# fretscanner-untangle2.net
KiCad netlist of a schematic drawn in EAGLE
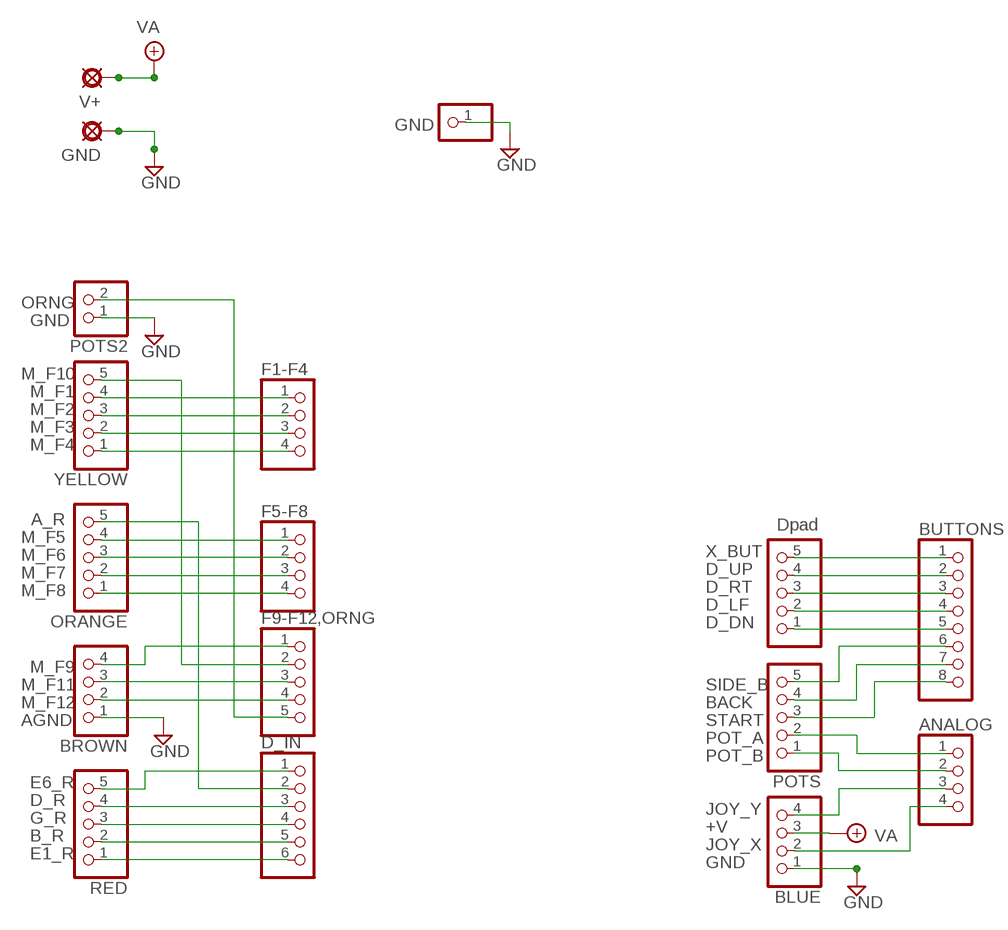
[diagram p0: schematic, sheet 1]

(export (version "E")
  (design (tool "Eeschema 10.0.6"))
  (components
    (comp (ref "ANALOG")
      (value "PINHD-1X4")
      (footprint "eagle-import:1X04")
      (libsource (lib "eagle-import") (part "PINHD-1X4"))
    )
    (comp (ref "BLUE")
      (value "PINHD-1X4")
      (footprint "eagle-import:1X04")
      (libsource (lib "eagle-import") (part "PINHD-1X4"))
    )
    (comp (ref "BROWN")
      (value "PINHD-1X4")
      (footprint "eagle-import:1X04")
      (libsource (lib "eagle-import") (part "PINHD-1X4"))
    )
    (comp (ref "BUTTONS")
      (value "PINHD-1X8")
      (footprint "eagle-import:1X08")
      (libsource (lib "eagle-import") (part "PINHD-1X8"))
    )
    (comp (ref "DPAD")
      (value "PINHD-1X5")
      (footprint "eagle-import:1X05")
      (libsource (lib "eagle-import") (part "PINHD-1X5"))
    )
    (comp (ref "DPAD2")
      (value "PINHD-1X1")
      (footprint "eagle-import:1X01")
      (libsource (lib "eagle-import") (part "PINHD-1X1"))
    )
    (comp (ref "D_IN")
      (value "PINHD-1X6")
      (footprint "eagle-import:1X06")
      (libsource (lib "eagle-import") (part "PINHD-1X6"))
    )
    (comp (ref "F1-F4")
      (value "PINHD-1X4")
      (footprint "eagle-import:1X04")
      (libsource (lib "eagle-import") (part "PINHD-1X4"))
    )
    (comp (ref "F5-F8")
      (value "PINHD-1X4")
      (footprint "eagle-import:1X04")
      (libsource (lib "eagle-import") (part "PINHD-1X4"))
    )
    (comp (ref "F9-F12,ORNG")
      (value "PINHD-1X5")
      (footprint "eagle-import:1X05")
      (libsource (lib "eagle-import") (part "PINHD-1X5"))
    )
    (comp (ref "GND")
      (value "PADL")
      (footprint "eagle-import:LONG")
      (libsource (lib "eagle-import") (part "PADL"))
    )
    (comp (ref "ORANGE")
      (value "PINHD-1X5")
      (footprint "eagle-import:1X05")
      (libsource (lib "eagle-import") (part "PINHD-1X5"))
    )
    (comp (ref "POTS")
      (value "PINHD-1X5")
      (footprint "eagle-import:1X05")
      (libsource (lib "eagle-import") (part "PINHD-1X5"))
    )
    (comp (ref "POTS2")
      (value "PINHD-1X2")
      (footprint "eagle-import:1X02")
      (libsource (lib "eagle-import") (part "PINHD-1X2"))
    )
    (comp (ref "RED")
      (value "PINHD-1X5")
      (footprint "eagle-import:1X05")
      (libsource (lib "eagle-import") (part "PINHD-1X5"))
    )
    (comp (ref "V+")
      (value "PADL")
      (footprint "eagle-import:LONG")
      (libsource (lib "eagle-import") (part "PADL"))
    )
    (comp (ref "YELLOW")
      (value "PINHD-1X5")
      (footprint "eagle-import:1X05")
      (libsource (lib "eagle-import") (part "PINHD-1X5"))
    )
  )
  (nets
    (net (code "1") (name "GND") (class "Default")
      (node (ref "BLUE") (pin "1") (pinfunction "1_1") (pintype "passive"))
      (node (ref "BROWN") (pin "1") (pinfunction "1_1") (pintype "passive"))
      (node (ref "DPAD2") (pin "1") (pinfunction "1_1") (pintype "passive"))
      (node (ref "GND") (pin "1") (pinfunction "PAD_1") (pintype "passive"))
      (node (ref "POTS2") (pin "1") (pinfunction "1_1") (pintype "passive"))
    )
    (net (code "2") (name "Net-(ANALOG-Pad1)") (class "Default")
      (node (ref "ANALOG") (pin "1") (pinfunction "1_1") (pintype "passive"))
      (node (ref "POTS") (pin "2") (pinfunction "2_2") (pintype "passive"))
    )
    (net (code "3") (name "Net-(ANALOG-Pad2)") (class "Default")
      (node (ref "ANALOG") (pin "2") (pinfunction "2_2") (pintype "passive"))
      (node (ref "POTS") (pin "1") (pinfunction "1_1") (pintype "passive"))
    )
    (net (code "4") (name "Net-(ANALOG-Pad3)") (class "Default")
      (node (ref "ANALOG") (pin "3") (pinfunction "3_3") (pintype "passive"))
      (node (ref "BLUE") (pin "4") (pinfunction "4_4") (pintype "passive"))
    )
    (net (code "5") (name "Net-(ANALOG-Pad4)") (class "Default")
      (node (ref "ANALOG") (pin "4") (pinfunction "4_4") (pintype "passive"))
      (node (ref "BLUE") (pin "2") (pinfunction "2_2") (pintype "passive"))
    )
    (net (code "6") (name "Net-(BROWN-Pad2)") (class "Default")
      (node (ref "BROWN") (pin "2") (pinfunction "2_2") (pintype "passive"))
      (node (ref "F9-F12,ORNG") (pin "4") (pinfunction "4_4") (pintype "passive"))
    )
    (net (code "7") (name "Net-(BROWN-Pad3)") (class "Default")
      (node (ref "BROWN") (pin "3") (pinfunction "3_3") (pintype "passive"))
      (node (ref "F9-F12,ORNG") (pin "3") (pinfunction "3_3") (pintype "passive"))
    )
    (net (code "8") (name "Net-(BROWN-Pad4)") (class "Default")
      (node (ref "BROWN") (pin "4") (pinfunction "4_4") (pintype "passive"))
      (node (ref "F9-F12,ORNG") (pin "1") (pinfunction "1_1") (pintype "passive"))
    )
    (net (code "9") (name "Net-(BUTTONS-Pad1)") (class "Default")
      (node (ref "BUTTONS") (pin "1") (pinfunction "1_1") (pintype "passive"))
      (node (ref "DPAD") (pin "5") (pinfunction "5_5") (pintype "passive"))
    )
    (net (code "10") (name "Net-(BUTTONS-Pad2)") (class "Default")
      (node (ref "BUTTONS") (pin "2") (pinfunction "2_2") (pintype "passive"))
      (node (ref "DPAD") (pin "4") (pinfunction "4_4") (pintype "passive"))
    )
    (net (code "11") (name "Net-(BUTTONS-Pad3)") (class "Default")
      (node (ref "BUTTONS") (pin "3") (pinfunction "3_3") (pintype "passive"))
      (node (ref "DPAD") (pin "3") (pinfunction "3_3") (pintype "passive"))
    )
    (net (code "12") (name "Net-(BUTTONS-Pad4)") (class "Default")
      (node (ref "BUTTONS") (pin "4") (pinfunction "4_4") (pintype "passive"))
      (node (ref "DPAD") (pin "2") (pinfunction "2_2") (pintype "passive"))
    )
    (net (code "13") (name "Net-(BUTTONS-Pad5)") (class "Default")
      (node (ref "BUTTONS") (pin "5") (pinfunction "5_5") (pintype "passive"))
      (node (ref "DPAD") (pin "1") (pinfunction "1_1") (pintype "passive"))
    )
    (net (code "14") (name "Net-(BUTTONS-Pad6)") (class "Default")
      (node (ref "BUTTONS") (pin "6") (pinfunction "6_6") (pintype "passive"))
      (node (ref "POTS") (pin "5") (pinfunction "5_5") (pintype "passive"))
    )
    (net (code "15") (name "Net-(BUTTONS-Pad7)") (class "Default")
      (node (ref "BUTTONS") (pin "7") (pinfunction "7_7") (pintype "passive"))
      (node (ref "POTS") (pin "4") (pinfunction "4_4") (pintype "passive"))
    )
    (net (code "16") (name "Net-(BUTTONS-Pad8)") (class "Default")
      (node (ref "BUTTONS") (pin "8") (pinfunction "8_8") (pintype "passive"))
      (node (ref "POTS") (pin "3") (pinfunction "3_3") (pintype "passive"))
    )
    (net (code "17") (name "Net-(D_IN-Pad1)") (class "Default")
      (node (ref "D_IN") (pin "1") (pinfunction "1_1") (pintype "passive"))
      (node (ref "RED") (pin "5") (pinfunction "5_5") (pintype "passive"))
    )
    (net (code "18") (name "Net-(D_IN-Pad2)") (class "Default")
      (node (ref "D_IN") (pin "2") (pinfunction "2_2") (pintype "passive"))
      (node (ref "ORANGE") (pin "5") (pinfunction "5_5") (pintype "passive"))
    )
    (net (code "19") (name "Net-(D_IN-Pad3)") (class "Default")
      (node (ref "D_IN") (pin "3") (pinfunction "3_3") (pintype "passive"))
      (node (ref "RED") (pin "4") (pinfunction "4_4") (pintype "passive"))
    )
    (net (code "20") (name "Net-(D_IN-Pad4)") (class "Default")
      (node (ref "D_IN") (pin "4") (pinfunction "4_4") (pintype "passive"))
      (node (ref "RED") (pin "3") (pinfunction "3_3") (pintype "passive"))
    )
    (net (code "21") (name "Net-(D_IN-Pad5)") (class "Default")
      (node (ref "D_IN") (pin "5") (pinfunction "5_5") (pintype "passive"))
      (node (ref "RED") (pin "2") (pinfunction "2_2") (pintype "passive"))
    )
    (net (code "22") (name "Net-(D_IN-Pad6)") (class "Default")
      (node (ref "D_IN") (pin "6") (pinfunction "6_6") (pintype "passive"))
      (node (ref "RED") (pin "1") (pinfunction "1_1") (pintype "passive"))
    )
    (net (code "23") (name "Net-(F1-F4-Pad1)") (class "Default")
      (node (ref "F1-F4") (pin "1") (pinfunction "1_1") (pintype "passive"))
      (node (ref "YELLOW") (pin "4") (pinfunction "4_4") (pintype "passive"))
    )
    (net (code "24") (name "Net-(F1-F4-Pad2)") (class "Default")
      (node (ref "F1-F4") (pin "2") (pinfunction "2_2") (pintype "passive"))
      (node (ref "YELLOW") (pin "3") (pinfunction "3_3") (pintype "passive"))
    )
    (net (code "25") (name "Net-(F1-F4-Pad3)") (class "Default")
      (node (ref "F1-F4") (pin "3") (pinfunction "3_3") (pintype "passive"))
      (node (ref "YELLOW") (pin "2") (pinfunction "2_2") (pintype "passive"))
    )
    (net (code "26") (name "Net-(F1-F4-Pad4)") (class "Default")
      (node (ref "F1-F4") (pin "4") (pinfunction "4_4") (pintype "passive"))
      (node (ref "YELLOW") (pin "1") (pinfunction "1_1") (pintype "passive"))
    )
    (net (code "27") (name "Net-(F5-F8-Pad1)") (class "Default")
      (node (ref "F5-F8") (pin "1") (pinfunction "1_1") (pintype "passive"))
      (node (ref "ORANGE") (pin "4") (pinfunction "4_4") (pintype "passive"))
    )
    (net (code "28") (name "Net-(F5-F8-Pad2)") (class "Default")
      (node (ref "F5-F8") (pin "2") (pinfunction "2_2") (pintype "passive"))
      (node (ref "ORANGE") (pin "3") (pinfunction "3_3") (pintype "passive"))
    )
    (net (code "29") (name "Net-(F5-F8-Pad3)") (class "Default")
      (node (ref "F5-F8") (pin "3") (pinfunction "3_3") (pintype "passive"))
      (node (ref "ORANGE") (pin "2") (pinfunction "2_2") (pintype "passive"))
    )
    (net (code "30") (name "Net-(F5-F8-Pad4)") (class "Default")
      (node (ref "F5-F8") (pin "4") (pinfunction "4_4") (pintype "passive"))
      (node (ref "ORANGE") (pin "1") (pinfunction "1_1") (pintype "passive"))
    )
    (net (code "31") (name "Net-(F9-F12,ORNG-Pad2)") (class "Default")
      (node (ref "F9-F12,ORNG") (pin "2") (pinfunction "2_2") (pintype "passive"))
      (node (ref "YELLOW") (pin "5") (pinfunction "5_5") (pintype "passive"))
    )
    (net (code "32") (name "Net-(F9-F12,ORNG-Pad5)") (class "Default")
      (node (ref "F9-F12,ORNG") (pin "5") (pinfunction "5_5") (pintype "passive"))
      (node (ref "POTS2") (pin "2") (pinfunction "2_2") (pintype "passive"))
    )
    (net (code "33") (name "VA") (class "Default")
      (node (ref "BLUE") (pin "3") (pinfunction "3_3") (pintype "passive"))
      (node (ref "V+") (pin "1") (pinfunction "PAD_1") (pintype "passive"))
    )
  )
)
